# PAGE1.net
KiCad netlist of a schematic drawn in EAGLE
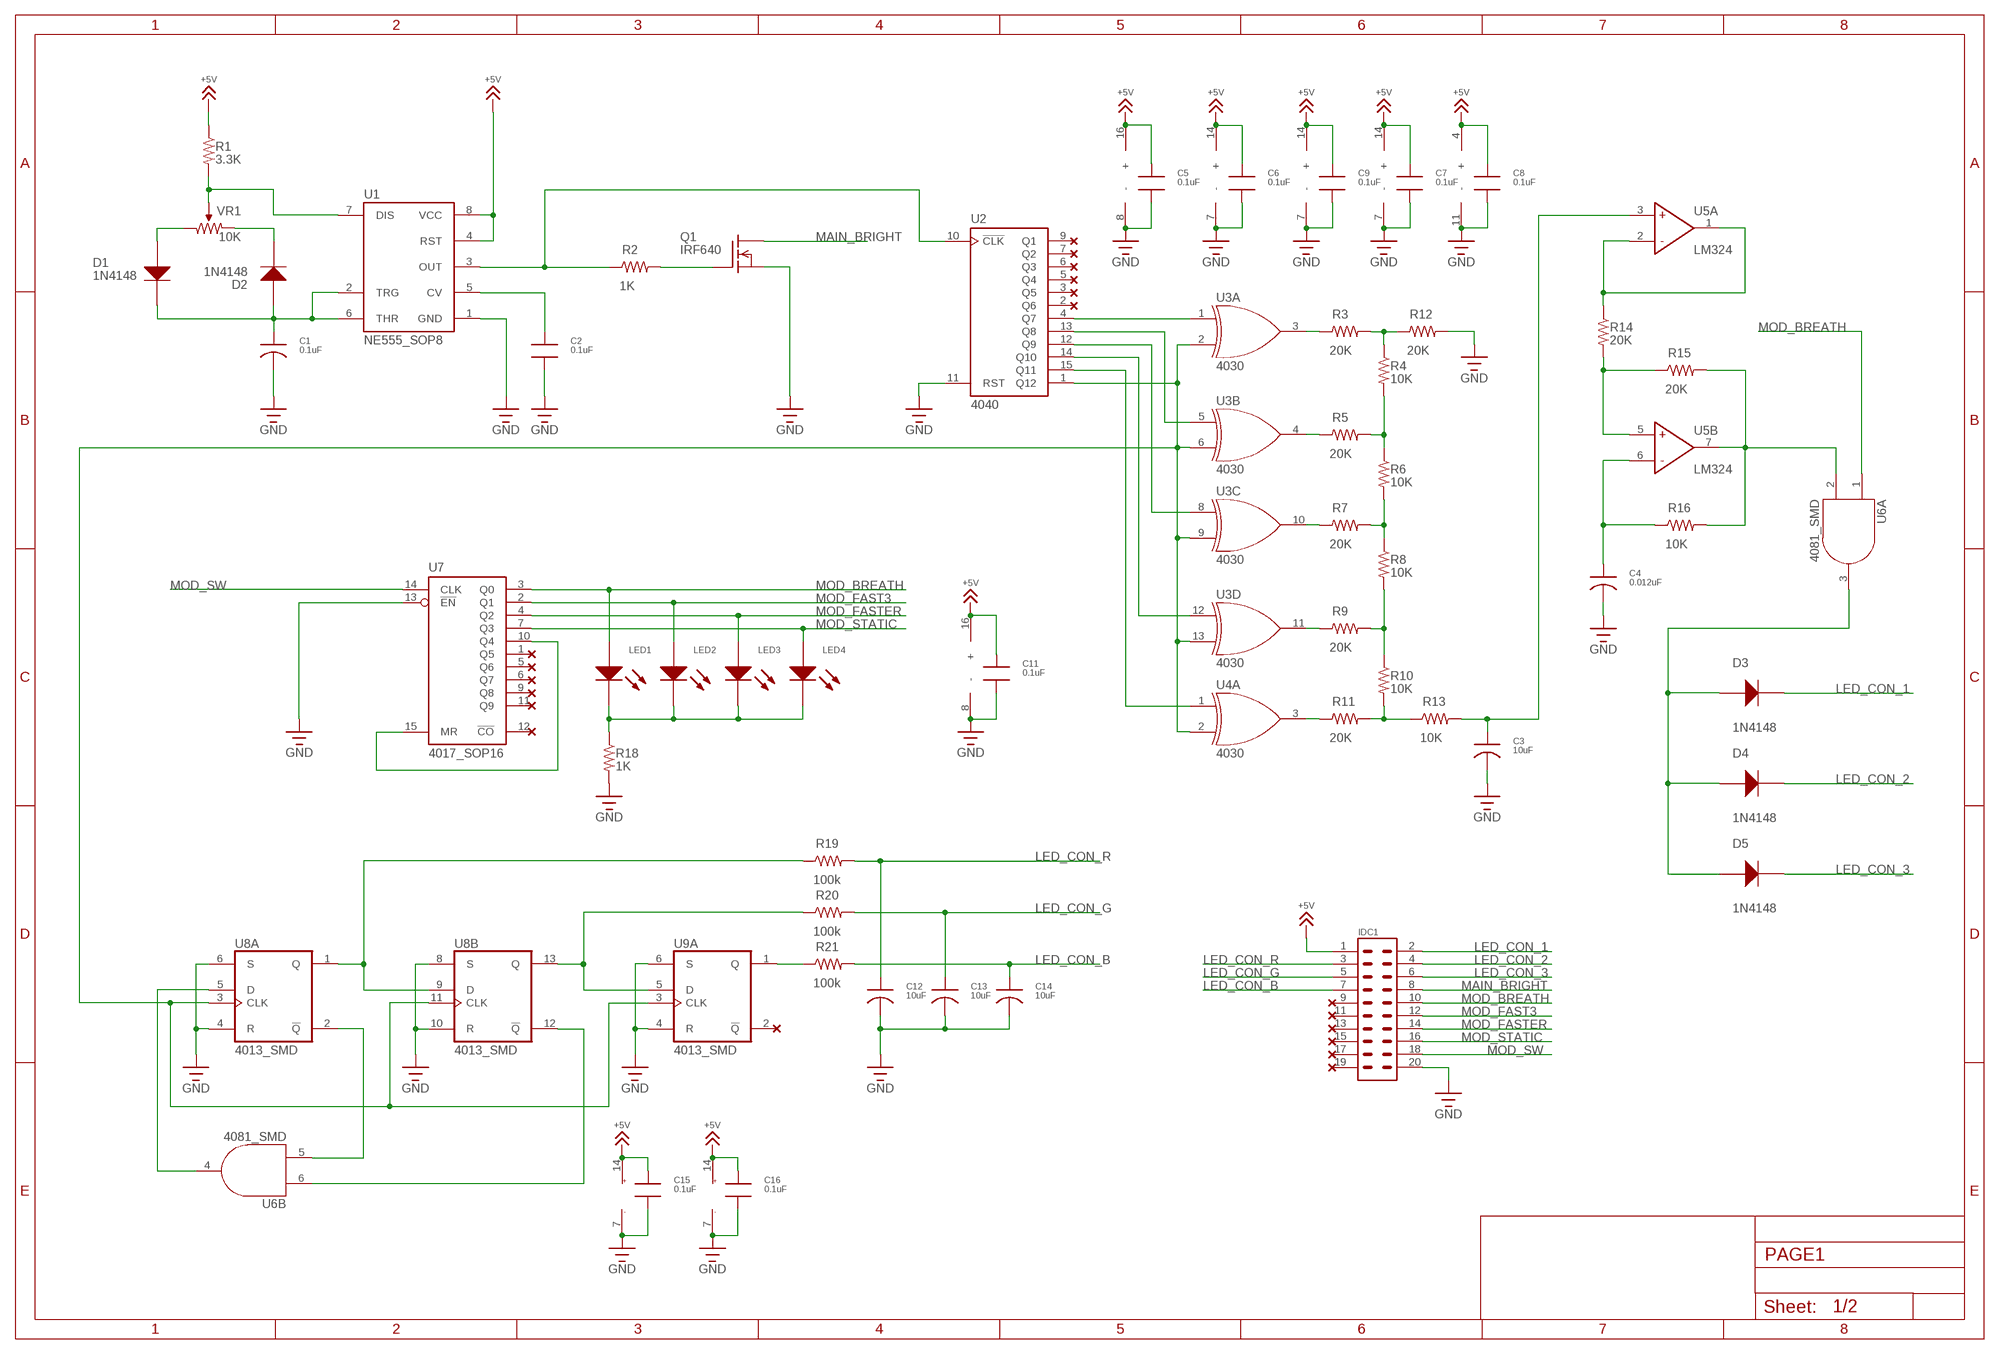
[diagram p0: schematic, sheet 1]
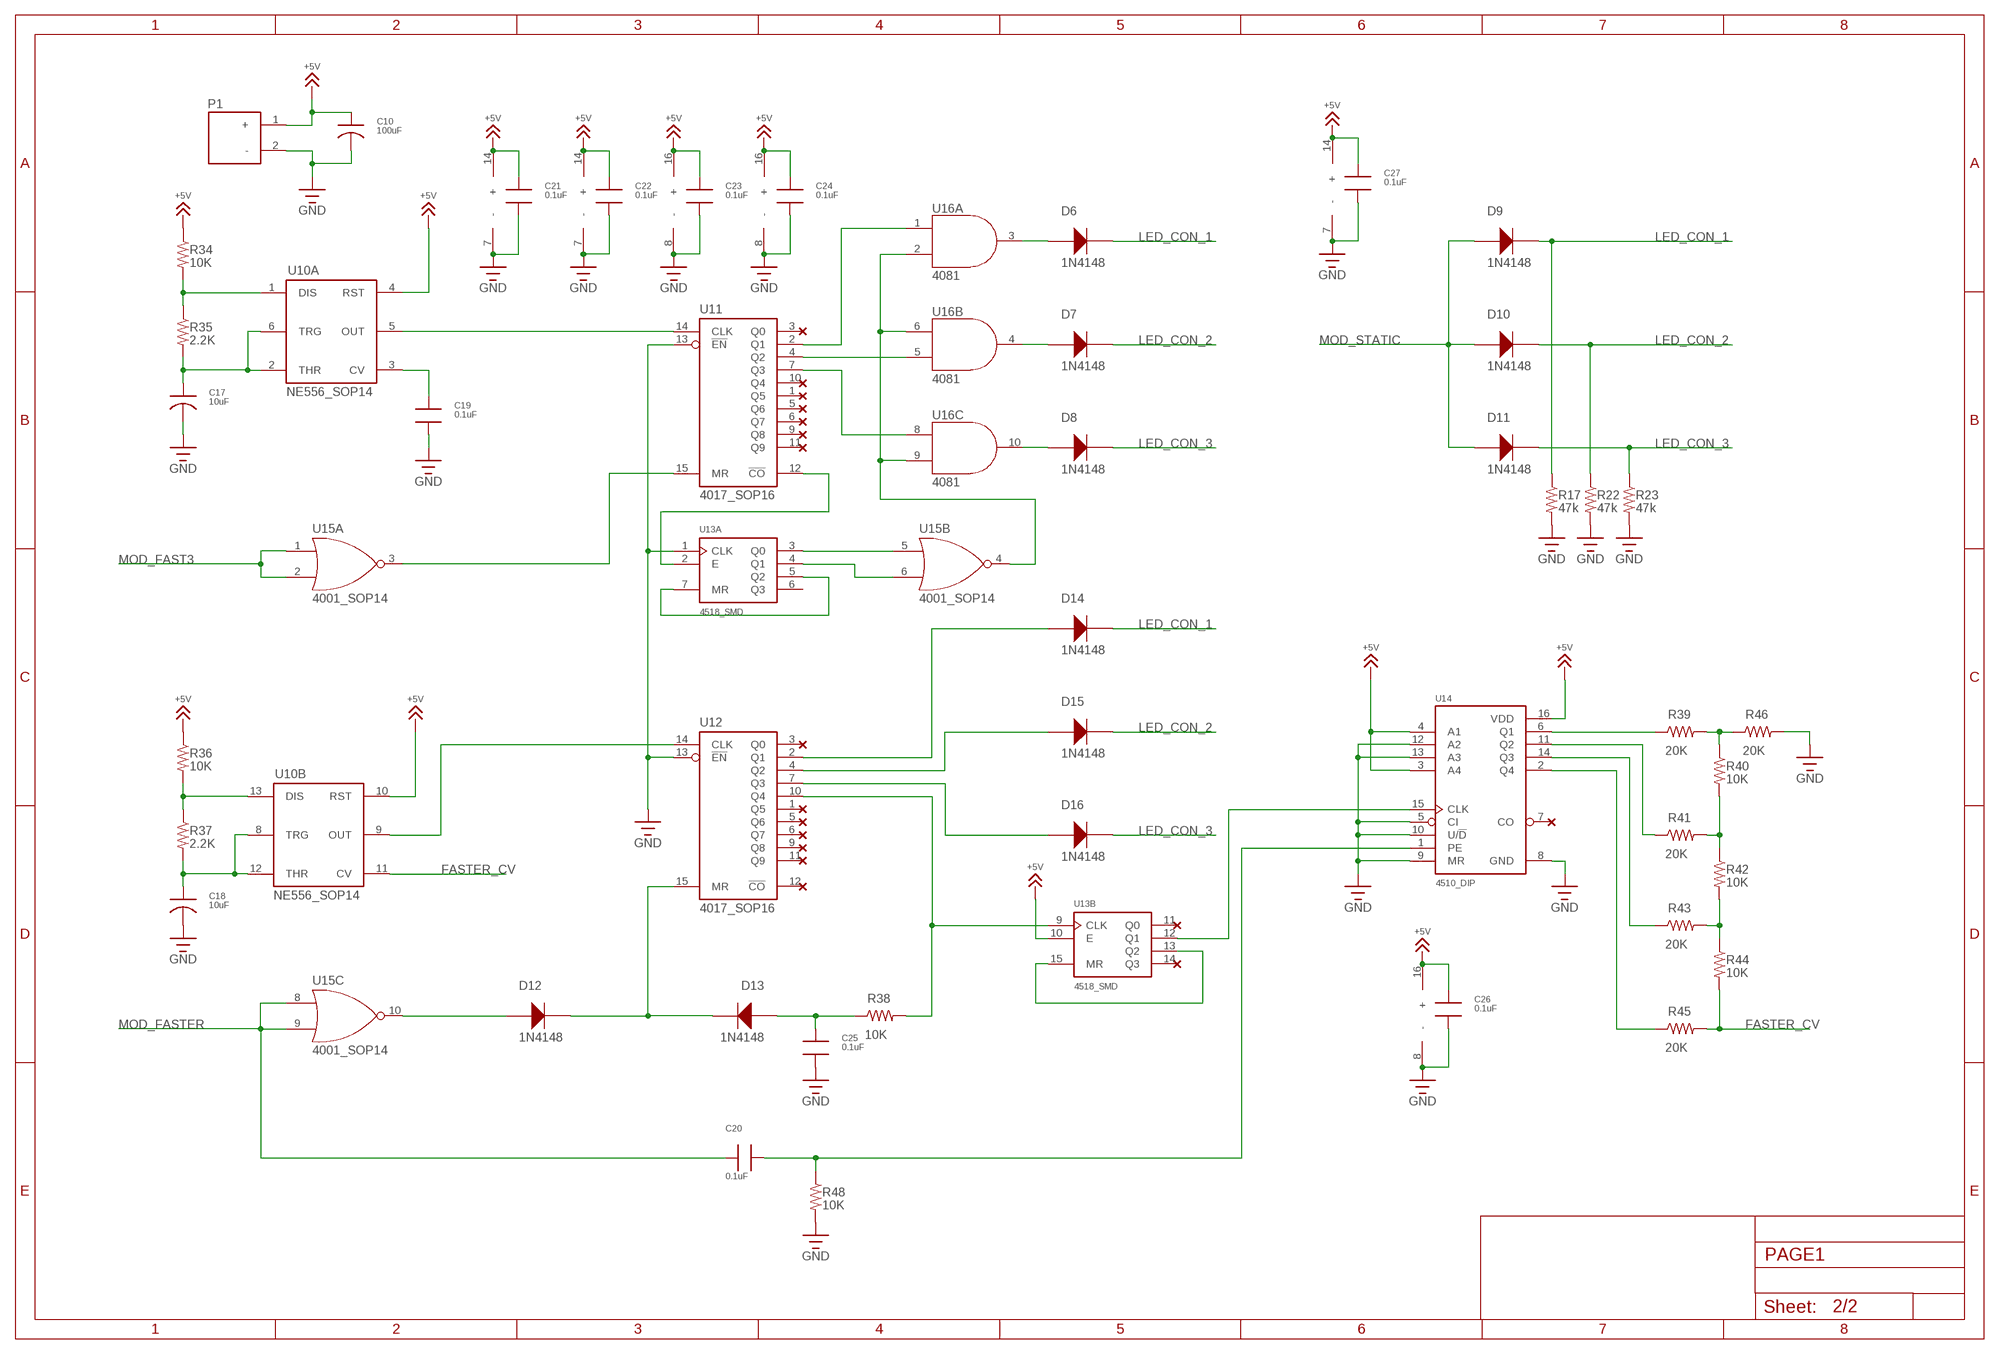
[diagram p1: schematic, sheet 2]

(export (version "E")
  (design (tool "Eeschema 10.0.6"))
  (components
    (comp (ref "C10")
      (value "100uF")
      (footprint "eagle-import:CAP_POL_BIG")
      (libsource (lib "eagle-import") (part "CAP_POL_BIG"))
    )
    (comp (ref "C17")
      (value "10uF")
      (footprint "eagle-import:CAP_POL")
      (libsource (lib "eagle-import") (part "CAP_POL_NOR"))
    )
    (comp (ref "C18")
      (value "10uF")
      (footprint "eagle-import:CAP_POL")
      (libsource (lib "eagle-import") (part "CAP_POL_NOR"))
    )
    (comp (ref "C19")
      (value "0.1uF")
      (footprint "eagle-import:SMD2012")
      (libsource (lib "eagle-import") (part "CAP_NP_SMD2012"))
    )
    (comp (ref "C20")
      (value "0.1uF")
      (footprint "eagle-import:SMD2012")
      (libsource (lib "eagle-import") (part "CAP_NP_SMD2012"))
    )
    (comp (ref "C21")
      (value "0.1uF")
      (footprint "eagle-import:SMD2012")
      (libsource (lib "eagle-import") (part "CAP_NP_SMD2012"))
    )
    (comp (ref "C22")
      (value "0.1uF")
      (footprint "eagle-import:SMD2012")
      (libsource (lib "eagle-import") (part "CAP_NP_SMD2012"))
    )
    (comp (ref "C23")
      (value "0.1uF")
      (footprint "eagle-import:SMD2012")
      (libsource (lib "eagle-import") (part "CAP_NP_SMD2012"))
    )
    (comp (ref "C24")
      (value "0.1uF")
      (footprint "eagle-import:SMD2012")
      (libsource (lib "eagle-import") (part "CAP_NP_SMD2012"))
    )
    (comp (ref "C25")
      (value "0.1uF")
      (footprint "eagle-import:SMD2012")
      (libsource (lib "eagle-import") (part "CAP_NP_SMD2012"))
    )
    (comp (ref "C26")
      (value "0.1uF")
      (footprint "eagle-import:SMD2012")
      (libsource (lib "eagle-import") (part "CAP_NP_SMD2012"))
    )
    (comp (ref "C27")
      (value "0.1uF")
      (footprint "eagle-import:SMD2012")
      (libsource (lib "eagle-import") (part "CAP_NP_SMD2012"))
    )
    (comp (ref "D6")
      (value "1N4148")
      (footprint "eagle-import:SMD_DIODE")
      (libsource (lib "eagle-import") (part "DIODE_SMD"))
    )
    (comp (ref "D7")
      (value "1N4148")
      (footprint "eagle-import:SMD_DIODE")
      (libsource (lib "eagle-import") (part "DIODE_SMD"))
    )
    (comp (ref "D8")
      (value "1N4148")
      (footprint "eagle-import:SMD_DIODE")
      (libsource (lib "eagle-import") (part "DIODE_SMD"))
    )
    (comp (ref "D9")
      (value "1N4148")
      (footprint "eagle-import:SMD_DIODE")
      (libsource (lib "eagle-import") (part "DIODE_SMD"))
    )
    (comp (ref "D10")
      (value "1N4148")
      (footprint "eagle-import:SMD_DIODE")
      (libsource (lib "eagle-import") (part "DIODE_SMD"))
    )
    (comp (ref "D11")
      (value "1N4148")
      (footprint "eagle-import:SMD_DIODE")
      (libsource (lib "eagle-import") (part "DIODE_SMD"))
    )
    (comp (ref "D12")
      (value "1N4148")
      (footprint "eagle-import:SMD_DIODE")
      (libsource (lib "eagle-import") (part "DIODE_SMD"))
    )
    (comp (ref "D13")
      (value "1N4148")
      (footprint "eagle-import:SMD_DIODE")
      (libsource (lib "eagle-import") (part "DIODE_SMD"))
    )
    (comp (ref "D14")
      (value "1N4148")
      (footprint "eagle-import:SMD_DIODE")
      (libsource (lib "eagle-import") (part "DIODE_SMD"))
    )
    (comp (ref "D15")
      (value "1N4148")
      (footprint "eagle-import:SMD_DIODE")
      (libsource (lib "eagle-import") (part "DIODE_SMD"))
    )
    (comp (ref "D16")
      (value "1N4148")
      (footprint "eagle-import:SMD_DIODE")
      (libsource (lib "eagle-import") (part "DIODE_SMD"))
    )
    (comp (ref "P1")
      (value "POWER_2")
      (footprint "eagle-import:POWER_2")
      (libsource (lib "eagle-import") (part "POWER_2"))
    )
    (comp (ref "R17")
      (value "47k")
      (footprint "eagle-import:SMD2012")
      (libsource (lib "eagle-import") (part "RES_2012"))
    )
    (comp (ref "R22")
      (value "47k")
      (footprint "eagle-import:SMD2012")
      (libsource (lib "eagle-import") (part "RES_2012"))
    )
    (comp (ref "R23")
      (value "47k")
      (footprint "eagle-import:SMD2012")
      (libsource (lib "eagle-import") (part "RES_2012"))
    )
    (comp (ref "R34")
      (value "10K")
      (footprint "eagle-import:SMD2012")
      (libsource (lib "eagle-import") (part "RES_2012"))
    )
    (comp (ref "R35")
      (value "2.2K")
      (footprint "eagle-import:SMD2012")
      (libsource (lib "eagle-import") (part "RES_2012"))
    )
    (comp (ref "R36")
      (value "10K")
      (footprint "eagle-import:SMD2012")
      (libsource (lib "eagle-import") (part "RES_2012"))
    )
    (comp (ref "R37")
      (value "2.2K")
      (footprint "eagle-import:SMD2012")
      (libsource (lib "eagle-import") (part "RES_2012"))
    )
    (comp (ref "R38")
      (value "10K")
      (footprint "eagle-import:SMD2012")
      (libsource (lib "eagle-import") (part "RES_2012"))
    )
    (comp (ref "R39")
      (value "20K")
      (footprint "eagle-import:SMD2012")
      (libsource (lib "eagle-import") (part "RES_2012"))
    )
    (comp (ref "R40")
      (value "10K")
      (footprint "eagle-import:SMD2012")
      (libsource (lib "eagle-import") (part "RES_2012"))
    )
    (comp (ref "R41")
      (value "20K")
      (footprint "eagle-import:SMD2012")
      (libsource (lib "eagle-import") (part "RES_2012"))
    )
    (comp (ref "R42")
      (value "10K")
      (footprint "eagle-import:SMD2012")
      (libsource (lib "eagle-import") (part "RES_2012"))
    )
    (comp (ref "R43")
      (value "20K")
      (footprint "eagle-import:SMD2012")
      (libsource (lib "eagle-import") (part "RES_2012"))
    )
    (comp (ref "R44")
      (value "10K")
      (footprint "eagle-import:SMD2012")
      (libsource (lib "eagle-import") (part "RES_2012"))
    )
    (comp (ref "R45")
      (value "20K")
      (footprint "eagle-import:SMD2012")
      (libsource (lib "eagle-import") (part "RES_2012"))
    )
    (comp (ref "R46")
      (value "20K")
      (footprint "eagle-import:SMD2012")
      (libsource (lib "eagle-import") (part "RES_2012"))
    )
    (comp (ref "R48")
      (value "10K")
      (footprint "eagle-import:SMD2012")
      (libsource (lib "eagle-import") (part "RES_2012"))
    )
    (comp (ref "U10")
      (value "NE556_SOP14")
      (footprint "eagle-import:SOP14")
      (libsource (lib "eagle-import") (part "NE556_SOP14"))
    )
    (comp (ref "U11")
      (value "4017_SOP16")
      (footprint "eagle-import:SOP16")
      (libsource (lib "eagle-import") (part "4017_SOP16"))
    )
    (comp (ref "U12")
      (value "4017_SOP16")
      (footprint "eagle-import:SOP16")
      (libsource (lib "eagle-import") (part "4017_SOP16"))
    )
    (comp (ref "U13")
      (value "4518_SMD")
      (footprint "eagle-import:SOP16")
      (libsource (lib "eagle-import") (part "4518_SMD"))
    )
    (comp (ref "U14")
      (value "4510_DIP")
      (footprint "eagle-import:DIP16")
      (libsource (lib "eagle-import") (part "4510_DIP"))
    )
    (comp (ref "U15")
      (value "4001_SOP14")
      (footprint "eagle-import:SOP14")
      (libsource (lib "eagle-import") (part "4001_SOP14"))
    )
    (comp (ref "U16")
      (value "4081")
      (footprint "eagle-import:DIP14")
      (libsource (lib "eagle-import") (part "4081"))
    )
    (comp (ref "C1")
      (value "0.1uF")
      (footprint "eagle-import:CAP_POL")
      (libsource (lib "eagle-import") (part "CAP_POL_NOR"))
    )
    (comp (ref "C2")
      (value "0.1uF")
      (footprint "eagle-import:SMD2012")
      (libsource (lib "eagle-import") (part "CAP_NP_SMD2012"))
    )
    (comp (ref "C3")
      (value "10uF")
      (footprint "eagle-import:CAP_POL")
      (libsource (lib "eagle-import") (part "CAP_POL_NOR"))
    )
    (comp (ref "C4")
      (value "0.012uF")
      (footprint "eagle-import:CAP_POL")
      (libsource (lib "eagle-import") (part "CAP_POL_NOR"))
    )
    (comp (ref "C5")
      (value "0.1uF")
      (footprint "eagle-import:SMD2012")
      (libsource (lib "eagle-import") (part "CAP_NP_SMD2012"))
    )
    (comp (ref "C6")
      (value "0.1uF")
      (footprint "eagle-import:SMD2012")
      (libsource (lib "eagle-import") (part "CAP_NP_SMD2012"))
    )
    (comp (ref "C7")
      (value "0.1uF")
      (footprint "eagle-import:SMD2012")
      (libsource (lib "eagle-import") (part "CAP_NP_SMD2012"))
    )
    (comp (ref "C8")
      (value "0.1uF")
      (footprint "eagle-import:SMD2012")
      (libsource (lib "eagle-import") (part "CAP_NP_SMD2012"))
    )
    (comp (ref "C9")
      (value "0.1uF")
      (footprint "eagle-import:SMD2012")
      (libsource (lib "eagle-import") (part "CAP_NP_SMD2012"))
    )
    (comp (ref "C11")
      (value "0.1uF")
      (footprint "eagle-import:SMD2012")
      (libsource (lib "eagle-import") (part "CAP_NP_SMD2012"))
    )
    (comp (ref "C12")
      (value "10uF")
      (footprint "eagle-import:CAP_POL")
      (libsource (lib "eagle-import") (part "CAP_POL_NOR"))
    )
    (comp (ref "C13")
      (value "10uF")
      (footprint "eagle-import:CAP_POL")
      (libsource (lib "eagle-import") (part "CAP_POL_NOR"))
    )
    (comp (ref "C14")
      (value "10uF")
      (footprint "eagle-import:CAP_POL")
      (libsource (lib "eagle-import") (part "CAP_POL_NOR"))
    )
    (comp (ref "C15")
      (value "0.1uF")
      (footprint "eagle-import:SMD2012")
      (libsource (lib "eagle-import") (part "CAP_NP_SMD2012"))
    )
    (comp (ref "C16")
      (value "0.1uF")
      (footprint "eagle-import:SMD2012")
      (libsource (lib "eagle-import") (part "CAP_NP_SMD2012"))
    )
    (comp (ref "D1")
      (value "1N4148")
      (footprint "eagle-import:SMD_DIODE")
      (libsource (lib "eagle-import") (part "DIODE_SMD"))
    )
    (comp (ref "D2")
      (value "1N4148")
      (footprint "eagle-import:SMD_DIODE")
      (libsource (lib "eagle-import") (part "DIODE_SMD"))
    )
    (comp (ref "D3")
      (value "1N4148")
      (footprint "eagle-import:SMD_DIODE")
      (libsource (lib "eagle-import") (part "DIODE_SMD"))
    )
    (comp (ref "D4")
      (value "1N4148")
      (footprint "eagle-import:SMD_DIODE")
      (libsource (lib "eagle-import") (part "DIODE_SMD"))
    )
    (comp (ref "D5")
      (value "1N4148")
      (footprint "eagle-import:SMD_DIODE")
      (libsource (lib "eagle-import") (part "DIODE_SMD"))
    )
    (comp (ref "IDC1")
      (value "IDC20_BEN")
      (footprint "eagle-import:IDC20_BENDING")
      (libsource (lib "eagle-import") (part "IDC20_BEN"))
    )
    (comp (ref "LED1")
      (value "LED_BEN")
      (footprint "eagle-import:LED_5MM_BEN")
      (libsource (lib "eagle-import") (part "LED_BEN"))
    )
    (comp (ref "LED2")
      (value "LED_BEN")
      (footprint "eagle-import:LED_5MM_BEN")
      (libsource (lib "eagle-import") (part "LED_BEN"))
    )
    (comp (ref "LED3")
      (value "LED_BEN")
      (footprint "eagle-import:LED_5MM_BEN")
      (libsource (lib "eagle-import") (part "LED_BEN"))
    )
    (comp (ref "LED4")
      (value "LED_BEN")
      (footprint "eagle-import:LED_5MM_BEN")
      (libsource (lib "eagle-import") (part "LED_BEN"))
    )
    (comp (ref "Q1")
      (value "IRF640")
      (footprint "eagle-import:TO220")
      (libsource (lib "eagle-import") (part "IRF620"))
    )
    (comp (ref "R1")
      (value "3.3K")
      (footprint "eagle-import:SMD2012")
      (libsource (lib "eagle-import") (part "RES_2012"))
    )
    (comp (ref "R2")
      (value "1K")
      (footprint "eagle-import:SMD2012")
      (libsource (lib "eagle-import") (part "RES_2012"))
    )
    (comp (ref "R3")
      (value "20K")
      (footprint "eagle-import:SMD2012")
      (libsource (lib "eagle-import") (part "RES_2012"))
    )
    (comp (ref "R4")
      (value "10K")
      (footprint "eagle-import:SMD2012")
      (libsource (lib "eagle-import") (part "RES_2012"))
    )
    (comp (ref "R5")
      (value "20K")
      (footprint "eagle-import:SMD2012")
      (libsource (lib "eagle-import") (part "RES_2012"))
    )
    (comp (ref "R6")
      (value "10K")
      (footprint "eagle-import:SMD2012")
      (libsource (lib "eagle-import") (part "RES_2012"))
    )
    (comp (ref "R7")
      (value "20K")
      (footprint "eagle-import:SMD2012")
      (libsource (lib "eagle-import") (part "RES_2012"))
    )
    (comp (ref "R8")
      (value "10K")
      (footprint "eagle-import:SMD2012")
      (libsource (lib "eagle-import") (part "RES_2012"))
    )
    (comp (ref "R9")
      (value "20K")
      (footprint "eagle-import:SMD2012")
      (libsource (lib "eagle-import") (part "RES_2012"))
    )
    (comp (ref "R10")
      (value "10K")
      (footprint "eagle-import:SMD2012")
      (libsource (lib "eagle-import") (part "RES_2012"))
    )
    (comp (ref "R11")
      (value "20K")
      (footprint "eagle-import:SMD2012")
      (libsource (lib "eagle-import") (part "RES_2012"))
    )
    (comp (ref "R12")
      (value "20K")
      (footprint "eagle-import:SMD2012")
      (libsource (lib "eagle-import") (part "RES_2012"))
    )
    (comp (ref "R13")
      (value "10K")
      (footprint "eagle-import:SMD2012")
      (libsource (lib "eagle-import") (part "RES_2012"))
    )
    (comp (ref "R14")
      (value "20K")
      (footprint "eagle-import:SMD2012")
      (libsource (lib "eagle-import") (part "RES_2012"))
    )
    (comp (ref "R15")
      (value "20K")
      (footprint "eagle-import:SMD2012")
      (libsource (lib "eagle-import") (part "RES_2012"))
    )
    (comp (ref "R16")
      (value "10K")
      (footprint "eagle-import:SMD2012")
      (libsource (lib "eagle-import") (part "RES_2012"))
    )
    (comp (ref "R18")
      (value "1K")
      (footprint "eagle-import:SMD2012")
      (libsource (lib "eagle-import") (part "RES_2012"))
    )
    (comp (ref "R19")
      (value "100k")
      (footprint "eagle-import:SMD2012")
      (libsource (lib "eagle-import") (part "RES_2012"))
    )
    (comp (ref "R20")
      (value "100k")
      (footprint "eagle-import:SMD2012")
      (libsource (lib "eagle-import") (part "RES_2012"))
    )
    (comp (ref "R21")
      (value "100k")
      (footprint "eagle-import:SMD2012")
      (libsource (lib "eagle-import") (part "RES_2012"))
    )
    (comp (ref "U1")
      (value "NE555_SOP8")
      (footprint "eagle-import:SOP8")
      (libsource (lib "eagle-import") (part "NE555_SOP8"))
    )
    (comp (ref "U2")
      (value "4040")
      (footprint "eagle-import:DIP16")
      (libsource (lib "eagle-import") (part "4040"))
    )
    (comp (ref "U3")
      (value "4030")
      (footprint "eagle-import:DIP14")
      (libsource (lib "eagle-import") (part "4030"))
    )
    (comp (ref "U4")
      (value "4030")
      (footprint "eagle-import:DIP14")
      (libsource (lib "eagle-import") (part "4030"))
    )
    (comp (ref "U5")
      (value "LM324")
      (footprint "eagle-import:DIP14")
      (libsource (lib "eagle-import") (part "LM324"))
    )
    (comp (ref "U6")
      (value "4081_SMD")
      (footprint "eagle-import:SOP14")
      (libsource (lib "eagle-import") (part "4081_SMD"))
    )
    (comp (ref "U7")
      (value "4017_SOP16")
      (footprint "eagle-import:SOP16")
      (libsource (lib "eagle-import") (part "4017_SOP16"))
    )
    (comp (ref "U8")
      (value "4013_SMD")
      (footprint "eagle-import:SOIC_14")
      (libsource (lib "eagle-import") (part "4013_SMD"))
    )
    (comp (ref "U9")
      (value "4013_SMD")
      (footprint "eagle-import:SOIC_14")
      (libsource (lib "eagle-import") (part "4013_SMD"))
    )
    (comp (ref "VR1")
      (value "10K")
      (footprint "eagle-import:3RP_1610N")
      (libsource (lib "eagle-import") (part "VR_BIG"))
    )
  )
  (nets
    (net (code "1") (name "+5V") (class "Default")
      (node (ref "C10") (pin "1") (pinfunction "1_1") (pintype "passive"))
      (node (ref "C11") (pin "1") (pinfunction "1_1") (pintype "passive"))
      (node (ref "C15") (pin "1") (pinfunction "1_1") (pintype "passive"))
      (node (ref "C16") (pin "1") (pinfunction "1_1") (pintype "passive"))
      (node (ref "C21") (pin "1") (pinfunction "1_1") (pintype "passive"))
      (node (ref "C22") (pin "1") (pinfunction "1_1") (pintype "passive"))
      (node (ref "C23") (pin "1") (pinfunction "1_1") (pintype "passive"))
      (node (ref "C24") (pin "1") (pinfunction "1_1") (pintype "passive"))
      (node (ref "C26") (pin "1") (pinfunction "1_1") (pintype "passive"))
      (node (ref "C27") (pin "1") (pinfunction "1_1") (pintype "passive"))
      (node (ref "C5") (pin "1") (pinfunction "1_1") (pintype "passive"))
      (node (ref "C6") (pin "1") (pinfunction "1_1") (pintype "passive"))
      (node (ref "C7") (pin "1") (pinfunction "1_1") (pintype "passive"))
      (node (ref "C8") (pin "1") (pinfunction "1_1") (pintype "passive"))
      (node (ref "C9") (pin "1") (pinfunction "1_1") (pintype "passive"))
      (node (ref "IDC1") (pin "1") (pinfunction "1_1") (pintype "passive"))
      (node (ref "P1") (pin "1") (pinfunction "+_1") (pintype "passive"))
      (node (ref "R1") (pin "1") (pinfunction "1_1") (pintype "passive"))
      (node (ref "R34") (pin "1") (pinfunction "1_1") (pintype "passive"))
      (node (ref "R36") (pin "1") (pinfunction "1_1") (pintype "passive"))
      (node (ref "U1") (pin "4") (pinfunction "RST_4") (pintype "passive"))
      (node (ref "U1") (pin "8") (pinfunction "VCC_8") (pintype "passive"))
      (node (ref "U10") (pin "10") (pinfunction "RST_10") (pintype "passive"))
      (node (ref "U10") (pin "14") (pinfunction "+_14") (pintype "power_in"))
      (node (ref "U10") (pin "4") (pinfunction "RST_4") (pintype "passive"))
      (node (ref "U11") (pin "16") (pinfunction "+_16") (pintype "power_in"))
      (node (ref "U12") (pin "16") (pinfunction "+_16") (pintype "power_in"))
      (node (ref "U13") (pin "10") (pinfunction "E_10") (pintype "passive"))
      (node (ref "U13") (pin "16") (pinfunction "+_16") (pintype "power_in"))
      (node (ref "U14") (pin "16") (pinfunction "VDD_16") (pintype "power_in"))
      (node (ref "U14") (pin "3") (pinfunction "A4_3") (pintype "input"))
      (node (ref "U14") (pin "4") (pinfunction "A1_4") (pintype "input"))
      (node (ref "U15") (pin "14") (pinfunction "+_14") (pintype "power_in"))
      (node (ref "U16") (pin "14") (pinfunction "+_14") (pintype "power_in"))
      (node (ref "U2") (pin "16") (pinfunction "+_16") (pintype "power_in"))
      (node (ref "U3") (pin "14") (pinfunction "+_14") (pintype "power_in"))
      (node (ref "U4") (pin "14") (pinfunction "+_14") (pintype "power_in"))
      (node (ref "U5") (pin "4") (pinfunction "+_4") (pintype "power_in"))
      (node (ref "U6") (pin "14") (pinfunction "+_14") (pintype "power_in"))
      (node (ref "U7") (pin "16") (pinfunction "+_16") (pintype "power_in"))
      (node (ref "U8") (pin "14") (pinfunction "VCC_14") (pintype "power_in"))
      (node (ref "U9") (pin "14") (pinfunction "VCC_14") (pintype "power_in"))
    )
    (net (code "2") (name "FASTER_CV") (class "Default")
      (node (ref "R44") (pin "2") (pinfunction "2_2") (pintype "passive"))
      (node (ref "R45") (pin "2") (pinfunction "2_2") (pintype "passive"))
      (node (ref "U10") (pin "11") (pinfunction "CV_11") (pintype "passive"))
    )
    (net (code "3") (name "GND") (class "Default")
      (node (ref "C1") (pin "2") (pinfunction "2_2") (pintype "passive"))
      (node (ref "C10") (pin "2") (pinfunction "2_2") (pintype "passive"))
      (node (ref "C11") (pin "2") (pinfunction "2_2") (pintype "passive"))
      (node (ref "C12") (pin "2") (pinfunction "2_2") (pintype "passive"))
      (node (ref "C13") (pin "2") (pinfunction "2_2") (pintype "passive"))
      (node (ref "C14") (pin "2") (pinfunction "2_2") (pintype "passive"))
      (node (ref "C15") (pin "2") (pinfunction "2_2") (pintype "passive"))
      (node (ref "C16") (pin "2") (pinfunction "2_2") (pintype "passive"))
      (node (ref "C17") (pin "2") (pinfunction "2_2") (pintype "passive"))
      (node (ref "C18") (pin "2") (pinfunction "2_2") (pintype "passive"))
      (node (ref "C19") (pin "2") (pinfunction "2_2") (pintype "passive"))
      (node (ref "C2") (pin "2") (pinfunction "2_2") (pintype "passive"))
      (node (ref "C21") (pin "2") (pinfunction "2_2") (pintype "passive"))
      (node (ref "C22") (pin "2") (pinfunction "2_2") (pintype "passive"))
      (node (ref "C23") (pin "2") (pinfunction "2_2") (pintype "passive"))
      (node (ref "C24") (pin "2") (pinfunction "2_2") (pintype "passive"))
      (node (ref "C25") (pin "2") (pinfunction "2_2") (pintype "passive"))
      (node (ref "C26") (pin "2") (pinfunction "2_2") (pintype "passive"))
      (node (ref "C27") (pin "2") (pinfunction "2_2") (pintype "passive"))
      (node (ref "C3") (pin "2") (pinfunction "2_2") (pintype "passive"))
      (node (ref "C4") (pin "2") (pinfunction "2_2") (pintype "passive"))
      (node (ref "C5") (pin "2") (pinfunction "2_2") (pintype "passive"))
      (node (ref "C6") (pin "2") (pinfunction "2_2") (pintype "passive"))
      (node (ref "C7") (pin "2") (pinfunction "2_2") (pintype "passive"))
      (node (ref "C8") (pin "2") (pinfunction "2_2") (pintype "passive"))
      (node (ref "C9") (pin "2") (pinfunction "2_2") (pintype "passive"))
      (node (ref "IDC1") (pin "20") (pinfunction "20_20") (pintype "passive"))
      (node (ref "P1") (pin "2") (pinfunction "-_2") (pintype "passive"))
      (node (ref "Q1") (pin "3") (pinfunction "S_3") (pintype "passive"))
      (node (ref "R12") (pin "2") (pinfunction "2_2") (pintype "passive"))
      (node (ref "R17") (pin "2") (pinfunction "2_2") (pintype "passive"))
      (node (ref "R18") (pin "2") (pinfunction "2_2") (pintype "passive"))
      (node (ref "R22") (pin "2") (pinfunction "2_2") (pintype "passive"))
      (node (ref "R23") (pin "2") (pinfunction "2_2") (pintype "passive"))
      (node (ref "R46") (pin "2") (pinfunction "2_2") (pintype "passive"))
      (node (ref "R48") (pin "2") (pinfunction "2_2") (pintype "passive"))
      (node (ref "U1") (pin "1") (pinfunction "GND_1") (pintype "passive"))
      (node (ref "U10") (pin "7") (pinfunction "-_7") (pintype "power_in"))
      (node (ref "U11") (pin "13") (pinfunction "~{EN}_13") (pintype "passive"))
      (node (ref "U11") (pin "8") (pinfunction "-_8") (pintype "power_in"))
      (node (ref "U12") (pin "13") (pinfunction "~{EN}_13") (pintype "passive"))
      (node (ref "U12") (pin "8") (pinfunction "-_8") (pintype "power_in"))
      (node (ref "U13") (pin "1") (pinfunction "CLK_1") (pintype "input"))
      (node (ref "U13") (pin "8") (pinfunction "-_8") (pintype "power_in"))
      (node (ref "U14") (pin "10") (pinfunction "U/~{D}_10") (pintype "passive"))
      (node (ref "U14") (pin "12") (pinfunction "A2_12") (pintype "input"))
      (node (ref "U14") (pin "13") (pinfunction "A3_13") (pintype "input"))
      (node (ref "U14") (pin "5") (pinfunction "CI_5") (pintype "input"))
      (node (ref "U14") (pin "8") (pinfunction "GND_8") (pintype "power_in"))
      (node (ref "U14") (pin "9") (pinfunction "MR_9") (pintype "passive"))
      (node (ref "U15") (pin "7") (pinfunction "-_7") (pintype "power_in"))
      (node (ref "U16") (pin "7") (pinfunction "-_7") (pintype "power_in"))
      (node (ref "U2") (pin "11") (pinfunction "RST_11") (pintype "input"))
      (node (ref "U2") (pin "8") (pinfunction "-_8") (pintype "power_in"))
      (node (ref "U3") (pin "7") (pinfunction "-_7") (pintype "power_in"))
      (node (ref "U4") (pin "7") (pinfunction "-_7") (pintype "power_in"))
      (node (ref "U5") (pin "11") (pinfunction "-_11") (pintype "power_in"))
      (node (ref "U6") (pin "7") (pinfunction "-_7") (pintype "power_in"))
      (node (ref "U7") (pin "13") (pinfunction "~{EN}_13") (pintype "passive"))
      (node (ref "U7") (pin "8") (pinfunction "-_8") (pintype "power_in"))
      (node (ref "U8") (pin "10") (pinfunction "R_10") (pintype "input"))
      (node (ref "U8") (pin "4") (pinfunction "R_4") (pintype "input"))
      (node (ref "U8") (pin "6") (pinfunction "S_6") (pintype "input"))
      (node (ref "U8") (pin "7") (pinfunction "GND_7") (pintype "power_in"))
      (node (ref "U8") (pin "8") (pinfunction "S_8") (pintype "input"))
      (node (ref "U9") (pin "4") (pinfunction "R_4") (pintype "input"))
      (node (ref "U9") (pin "6") (pinfunction "S_6") (pintype "input"))
      (node (ref "U9") (pin "7") (pinfunction "GND_7") (pintype "power_in"))
    )
    (net (code "4") (name "LED_CON_1") (class "Default")
      (node (ref "D14") (pin "2") (pinfunction "2_2") (pintype "passive"))
      (node (ref "D3") (pin "2") (pinfunction "2_2") (pintype "passive"))
      (node (ref "D6") (pin "2") (pinfunction "2_2") (pintype "passive"))
      (node (ref "D9") (pin "2") (pinfunction "2_2") (pintype "passive"))
      (node (ref "IDC1") (pin "2") (pinfunction "2_2") (pintype "passive"))
      (node (ref "R17") (pin "1") (pinfunction "1_1") (pintype "passive"))
    )
    (net (code "5") (name "LED_CON_2") (class "Default")
      (node (ref "D10") (pin "2") (pinfunction "2_2") (pintype "passive"))
      (node (ref "D15") (pin "2") (pinfunction "2_2") (pintype "passive"))
      (node (ref "D4") (pin "2") (pinfunction "2_2") (pintype "passive"))
      (node (ref "D7") (pin "2") (pinfunction "2_2") (pintype "passive"))
      (node (ref "IDC1") (pin "4") (pinfunction "4_4") (pintype "passive"))
      (node (ref "R22") (pin "1") (pinfunction "1_1") (pintype "passive"))
    )
    (net (code "6") (name "LED_CON_3") (class "Default")
      (node (ref "D11") (pin "2") (pinfunction "2_2") (pintype "passive"))
      (node (ref "D16") (pin "2") (pinfunction "2_2") (pintype "passive"))
      (node (ref "D5") (pin "2") (pinfunction "2_2") (pintype "passive"))
      (node (ref "D8") (pin "2") (pinfunction "2_2") (pintype "passive"))
      (node (ref "IDC1") (pin "6") (pinfunction "6_6") (pintype "passive"))
      (node (ref "R23") (pin "1") (pinfunction "1_1") (pintype "passive"))
    )
    (net (code "7") (name "LED_CON_B") (class "Default")
      (node (ref "C14") (pin "1") (pinfunction "1_1") (pintype "passive"))
      (node (ref "IDC1") (pin "7") (pinfunction "7_7") (pintype "passive"))
      (node (ref "R21") (pin "2") (pinfunction "2_2") (pintype "passive"))
    )
    (net (code "8") (name "LED_CON_G") (class "Default")
      (node (ref "C13") (pin "1") (pinfunction "1_1") (pintype "passive"))
      (node (ref "IDC1") (pin "5") (pinfunction "5_5") (pintype "passive"))
      (node (ref "R20") (pin "2") (pinfunction "2_2") (pintype "passive"))
    )
    (net (code "9") (name "LED_CON_R") (class "Default")
      (node (ref "C12") (pin "1") (pinfunction "1_1") (pintype "passive"))
      (node (ref "IDC1") (pin "3") (pinfunction "3_3") (pintype "passive"))
      (node (ref "R19") (pin "2") (pinfunction "2_2") (pintype "passive"))
    )
    (net (code "10") (name "MAIN_BRIGHT") (class "Default")
      (node (ref "IDC1") (pin "8") (pinfunction "8_8") (pintype "passive"))
      (node (ref "Q1") (pin "2") (pinfunction "D_2") (pintype "passive"))
    )
    (net (code "11") (name "MOD_BREATH") (class "Default")
      (node (ref "IDC1") (pin "10") (pinfunction "10_10") (pintype "passive"))
      (node (ref "LED1") (pin "1") (pinfunction "P$1_1") (pintype "passive"))
      (node (ref "U6") (pin "1") (pinfunction "P$1_1") (pintype "passive"))
      (node (ref "U7") (pin "3") (pinfunction "Q0_3") (pintype "output"))
    )
    (net (code "12") (name "MOD_FAST3") (class "Default")
      (node (ref "IDC1") (pin "12") (pinfunction "12_12") (pintype "passive"))
      (node (ref "LED2") (pin "1") (pinfunction "P$1_1") (pintype "passive"))
      (node (ref "U15") (pin "1") (pinfunction "IN1_1") (pintype "passive"))
      (node (ref "U15") (pin "2") (pinfunction "IN2_2") (pintype "passive"))
      (node (ref "U7") (pin "2") (pinfunction "Q1_2") (pintype "output"))
    )
    (net (code "13") (name "MOD_FASTER") (class "Default")
      (node (ref "C20") (pin "1") (pinfunction "1_1") (pintype "passive"))
      (node (ref "IDC1") (pin "14") (pinfunction "14_14") (pintype "passive"))
      (node (ref "LED3") (pin "1") (pinfunction "P$1_1") (pintype "passive"))
      (node (ref "U15") (pin "8") (pinfunction "IN1_8") (pintype "passive"))
      (node (ref "U15") (pin "9") (pinfunction "IN2_9") (pintype "passive"))
      (node (ref "U7") (pin "4") (pinfunction "Q2_4") (pintype "output"))
    )
    (net (code "14") (name "MOD_STATIC") (class "Default")
      (node (ref "D10") (pin "1") (pinfunction "1_1") (pintype "passive"))
      (node (ref "D11") (pin "1") (pinfunction "1_1") (pintype "passive"))
      (node (ref "D9") (pin "1") (pinfunction "1_1") (pintype "passive"))
      (node (ref "IDC1") (pin "16") (pinfunction "16_16") (pintype "passive"))
      (node (ref "LED4") (pin "1") (pinfunction "P$1_1") (pintype "passive"))
      (node (ref "U7") (pin "7") (pinfunction "Q3_7") (pintype "output"))
    )
    (net (code "15") (name "MOD_SW") (class "Default")
      (node (ref "IDC1") (pin "18") (pinfunction "18_18") (pintype "passive"))
      (node (ref "U7") (pin "14") (pinfunction "CLK_14") (pintype "passive"))
    )
    (net (code "16") (name "Net-(C25-Pad1)") (class "Default")
      (node (ref "C25") (pin "1") (pinfunction "1_1") (pintype "passive"))
      (node (ref "D13") (pin "1") (pinfunction "1_1") (pintype "passive"))
      (node (ref "R38") (pin "1") (pinfunction "1_1") (pintype "passive"))
    )
    (net (code "17") (name "Net-(D1-Pad1)") (class "Default")
      (node (ref "D1") (pin "1") (pinfunction "1_1") (pintype "passive"))
      (node (ref "VR1") (pin "1") (pinfunction "1_1") (pintype "passive"))
    )
    (net (code "18") (name "Net-(D2-Pad2)") (class "Default")
      (node (ref "D2") (pin "2") (pinfunction "2_2") (pintype "passive"))
      (node (ref "VR1") (pin "3") (pinfunction "3_3") (pintype "passive"))
    )
    (net (code "19") (name "Net-(LED1-P$2)") (class "Default")
      (node (ref "LED1") (pin "2") (pinfunction "P$2_2") (pintype "passive"))
      (node (ref "LED2") (pin "2") (pinfunction "P$2_2") (pintype "passive"))
      (node (ref "LED3") (pin "2") (pinfunction "P$2_2") (pintype "passive"))
      (node (ref "LED4") (pin "2") (pinfunction "P$2_2") (pintype "passive"))
      (node (ref "R18") (pin "1") (pinfunction "1_1") (pintype "passive"))
    )
    (net (code "20") (name "Net-(Q1-G)") (class "Default")
      (node (ref "Q1") (pin "1") (pinfunction "G_1") (pintype "passive"))
      (node (ref "R2") (pin "2") (pinfunction "2_2") (pintype "passive"))
    )
    (net (code "21") (name "Net-(R4-Pad2)") (class "Default")
      (node (ref "R4") (pin "2") (pinfunction "2_2") (pintype "passive"))
      (node (ref "R5") (pin "2") (pinfunction "2_2") (pintype "passive"))
      (node (ref "R6") (pin "1") (pinfunction "1_1") (pintype "passive"))
    )
    (net (code "22") (name "Net-(R6-Pad2)") (class "Default")
      (node (ref "R6") (pin "2") (pinfunction "2_2") (pintype "passive"))
      (node (ref "R7") (pin "2") (pinfunction "2_2") (pintype "passive"))
      (node (ref "R8") (pin "1") (pinfunction "1_1") (pintype "passive"))
    )
    (net (code "23") (name "Net-(R10-Pad1)") (class "Default")
      (node (ref "R10") (pin "1") (pinfunction "1_1") (pintype "passive"))
      (node (ref "R8") (pin "2") (pinfunction "2_2") (pintype "passive"))
      (node (ref "R9") (pin "2") (pinfunction "2_2") (pintype "passive"))
    )
    (net (code "24") (name "Net-(R10-Pad2)") (class "Default")
      (node (ref "R10") (pin "2") (pinfunction "2_2") (pintype "passive"))
      (node (ref "R11") (pin "2") (pinfunction "2_2") (pintype "passive"))
      (node (ref "R13") (pin "1") (pinfunction "1_1") (pintype "passive"))
    )
    (net (code "25") (name "Net-(R12-Pad1)") (class "Default")
      (node (ref "R12") (pin "1") (pinfunction "1_1") (pintype "passive"))
      (node (ref "R3") (pin "2") (pinfunction "2_2") (pintype "passive"))
      (node (ref "R4") (pin "1") (pinfunction "1_1") (pintype "passive"))
    )
    (net (code "26") (name "Net-(R39-Pad2)") (class "Default")
      (node (ref "R39") (pin "2") (pinfunction "2_2") (pintype "passive"))
      (node (ref "R40") (pin "1") (pinfunction "1_1") (pintype "passive"))
      (node (ref "R46") (pin "1") (pinfunction "1_1") (pintype "passive"))
    )
    (net (code "27") (name "Net-(R40-Pad2)") (class "Default")
      (node (ref "R40") (pin "2") (pinfunction "2_2") (pintype "passive"))
      (node (ref "R41") (pin "2") (pinfunction "2_2") (pintype "passive"))
      (node (ref "R42") (pin "1") (pinfunction "1_1") (pintype "passive"))
    )
    (net (code "28") (name "Net-(R42-Pad2)") (class "Default")
      (node (ref "R42") (pin "2") (pinfunction "2_2") (pintype "passive"))
      (node (ref "R43") (pin "2") (pinfunction "2_2") (pintype "passive"))
      (node (ref "R44") (pin "1") (pinfunction "1_1") (pintype "passive"))
    )
    (net (code "29") (name "Net-(U1-CV)") (class "Default")
      (node (ref "C2") (pin "1") (pinfunction "1_1") (pintype "passive"))
      (node (ref "U1") (pin "5") (pinfunction "CV_5") (pintype "passive"))
    )
    (net (code "30") (name "Net-(U1-DIS)") (class "Default")
      (node (ref "R1") (pin "2") (pinfunction "2_2") (pintype "passive"))
      (node (ref "U1") (pin "7") (pinfunction "DIS_7") (pintype "passive"))
      (node (ref "VR1") (pin "2") (pinfunction "2_2") (pintype "passive"))
    )
    (net (code "31") (name "Net-(U1-OUT)") (class "Default")
      (node (ref "R2") (pin "1") (pinfunction "1_1") (pintype "passive"))
      (node (ref "U1") (pin "3") (pinfunction "OUT_3") (pintype "passive"))
      (node (ref "U2") (pin "10") (pinfunction "~{CLK}_10") (pintype "input"))
    )
    (net (code "32") (name "Net-(U1-THR)") (class "Default")
      (node (ref "C1") (pin "1") (pinfunction "1_1") (pintype "passive"))
      (node (ref "D1") (pin "2") (pinfunction "2_2") (pintype "passive"))
      (node (ref "D2") (pin "1") (pinfunction "1_1") (pintype "passive"))
      (node (ref "U1") (pin "2") (pinfunction "TRG_2") (pintype "passive"))
      (node (ref "U1") (pin "6") (pinfunction "THR_6") (pintype "passive"))
    )
    (net (code "33") (name "Net-(U2A-Q7)") (class "Default")
      (node (ref "U2") (pin "4") (pinfunction "Q7_4") (pintype "output"))
      (node (ref "U3") (pin "1") (pinfunction "IN1_1") (pintype "passive"))
    )
    (net (code "34") (name "Net-(U2A-Q8)") (class "Default")
      (node (ref "U2") (pin "13") (pinfunction "Q8_13") (pintype "output"))
      (node (ref "U3") (pin "5") (pinfunction "IN1_5") (pintype "passive"))
    )
    (net (code "35") (name "Net-(U2A-Q9)") (class "Default")
      (node (ref "U2") (pin "12") (pinfunction "Q9_12") (pintype "output"))
      (node (ref "U3") (pin "8") (pinfunction "IN1_8") (pintype "passive"))
    )
    (net (code "36") (name "Net-(U2A-Q10)") (class "Default")
      (node (ref "U2") (pin "14") (pinfunction "Q10_14") (pintype "output"))
      (node (ref "U3") (pin "12") (pinfunction "IN1_12") (pintype "passive"))
    )
    (net (code "37") (name "Net-(U2A-Q11)") (class "Default")
      (node (ref "U2") (pin "15") (pinfunction "Q11_15") (pintype "output"))
      (node (ref "U4") (pin "1") (pinfunction "IN1_1") (pintype "passive"))
    )
    (net (code "38") (name "Net-(U2A-Q12)") (class "Default")
      (node (ref "U2") (pin "1") (pinfunction "Q12_1") (pintype "output"))
      (node (ref "U3") (pin "13") (pinfunction "IN2_13") (pintype "passive"))
      (node (ref "U3") (pin "2") (pinfunction "IN2_2") (pintype "passive"))
      (node (ref "U3") (pin "6") (pinfunction "IN2_6") (pintype "passive"))
      (node (ref "U3") (pin "9") (pinfunction "IN2_9") (pintype "passive"))
      (node (ref "U4") (pin "2") (pinfunction "IN2_2") (pintype "passive"))
      (node (ref "U8") (pin "11") (pinfunction "CLK_11") (pintype "input"))
      (node (ref "U8") (pin "3") (pinfunction "CLK_3") (pintype "input"))
      (node (ref "U9") (pin "3") (pinfunction "CLK_3") (pintype "input"))
    )
    (net (code "39") (name "Net-(U3A-OUT)") (class "Default")
      (node (ref "R3") (pin "1") (pinfunction "1_1") (pintype "passive"))
      (node (ref "U3") (pin "3") (pinfunction "OUT_3") (pintype "passive"))
    )
    (net (code "40") (name "Net-(U3B-OUT)") (class "Default")
      (node (ref "R5") (pin "1") (pinfunction "1_1") (pintype "passive"))
      (node (ref "U3") (pin "4") (pinfunction "OUT_4") (pintype "passive"))
    )
    (net (code "41") (name "Net-(U3C-OUT)") (class "Default")
      (node (ref "R7") (pin "1") (pinfunction "1_1") (pintype "passive"))
      (node (ref "U3") (pin "10") (pinfunction "OUT_10") (pintype "passive"))
    )
    (net (code "42") (name "Net-(U3D-OUT)") (class "Default")
      (node (ref "R9") (pin "1") (pinfunction "1_1") (pintype "passive"))
      (node (ref "U3") (pin "11") (pinfunction "OUT_11") (pintype "passive"))
    )
    (net (code "43") (name "Net-(U4A-OUT)") (class "Default")
      (node (ref "R11") (pin "1") (pinfunction "1_1") (pintype "passive"))
      (node (ref "U4") (pin "3") (pinfunction "OUT_3") (pintype "passive"))
    )
    (net (code "44") (name "Net-(U5A-+)") (class "Default")
      (node (ref "C3") (pin "1") (pinfunction "1_1") (pintype "passive"))
      (node (ref "R13") (pin "2") (pinfunction "2_2") (pintype "passive"))
      (node (ref "U5") (pin "3") (pinfunction "+_3") (pintype "input"))
    )
    (net (code "45") (name "Net-(U5A--)") (class "Default")
      (node (ref "R14") (pin "1") (pinfunction "1_1") (pintype "passive"))
      (node (ref "U5") (pin "1") (pinfunction "OUT_1") (pintype "output"))
      (node (ref "U5") (pin "2") (pinfunction "-_2") (pintype "input"))
    )
    (net (code "46") (name "Net-(U5B-+)") (class "Default")
      (node (ref "R14") (pin "2") (pinfunction "2_2") (pintype "passive"))
      (node (ref "R15") (pin "1") (pinfunction "1_1") (pintype "passive"))
      (node (ref "U5") (pin "5") (pinfunction "+_5") (pintype "input"))
    )
    (net (code "47") (name "Net-(U5B--)") (class "Default")
      (node (ref "C4") (pin "1") (pinfunction "1_1") (pintype "passive"))
      (node (ref "R16") (pin "1") (pinfunction "1_1") (pintype "passive"))
      (node (ref "U5") (pin "6") (pinfunction "-_6") (pintype "input"))
    )
    (net (code "48") (name "Net-(U5B-OUT)") (class "Default")
      (node (ref "R15") (pin "2") (pinfunction "2_2") (pintype "passive"))
      (node (ref "R16") (pin "2") (pinfunction "2_2") (pintype "passive"))
      (node (ref "U5") (pin "7") (pinfunction "OUT_7") (pintype "output"))
      (node (ref "U6") (pin "2") (pinfunction "P$2_2") (pintype "passive"))
    )
    (net (code "49") (name "Net-(U6A-P$3)") (class "Default")
      (node (ref "D3") (pin "1") (pinfunction "1_1") (pintype "passive"))
      (node (ref "D4") (pin "1") (pinfunction "1_1") (pintype "passive"))
      (node (ref "D5") (pin "1") (pinfunction "1_1") (pintype "passive"))
      (node (ref "U6") (pin "3") (pinfunction "P$3_3") (pintype "passive"))
    )
    (net (code "50") (name "Net-(U6B-P$1)") (class "Default")
      (node (ref "U6") (pin "6") (pinfunction "P$1_6") (pintype "passive"))
      (node (ref "U8") (pin "12") (pinfunction "~{Q}_12") (pintype "output"))
    )
    (net (code "51") (name "Net-(U6B-P$2)") (class "Default")
      (node (ref "U6") (pin "5") (pinfunction "P$2_5") (pintype "passive"))
      (node (ref "U8") (pin "2") (pinfunction "~{Q}_2") (pintype "output"))
    )
    (net (code "52") (name "Net-(U6B-P$3)") (class "Default")
      (node (ref "U6") (pin "4") (pinfunction "P$3_4") (pintype "passive"))
      (node (ref "U8") (pin "5") (pinfunction "D_5") (pintype "input"))
    )
    (net (code "53") (name "Net-(U7A-MR)") (class "Default")
      (node (ref "U7") (pin "10") (pinfunction "Q4_10") (pintype "output"))
      (node (ref "U7") (pin "15") (pinfunction "MR_15") (pintype "passive"))
    )
    (net (code "54") (name "Net-(U8A-Q)") (class "Default")
      (node (ref "R19") (pin "1") (pinfunction "1_1") (pintype "passive"))
      (node (ref "U8") (pin "1") (pinfunction "Q_1") (pintype "output"))
      (node (ref "U8") (pin "9") (pinfunction "D_9") (pintype "input"))
    )
    (net (code "55") (name "Net-(U8B-Q)") (class "Default")
      (node (ref "R20") (pin "1") (pinfunction "1_1") (pintype "passive"))
      (node (ref "U8") (pin "13") (pinfunction "Q_13") (pintype "output"))
      (node (ref "U9") (pin "5") (pinfunction "D_5") (pintype "input"))
    )
    (net (code "56") (name "Net-(U9A-Q)") (class "Default")
      (node (ref "R21") (pin "1") (pinfunction "1_1") (pintype "passive"))
      (node (ref "U9") (pin "1") (pinfunction "Q_1") (pintype "output"))
    )
    (net (code "57") (name "Net-(U10A-CV)") (class "Default")
      (node (ref "C19") (pin "1") (pinfunction "1_1") (pintype "passive"))
      (node (ref "U10") (pin "3") (pinfunction "CV_3") (pintype "passive"))
    )
    (net (code "58") (name "Net-(U10A-DIS)") (class "Default")
      (node (ref "R34") (pin "2") (pinfunction "2_2") (pintype "passive"))
      (node (ref "R35") (pin "1") (pinfunction "1_1") (pintype "passive"))
      (node (ref "U10") (pin "1") (pinfunction "DIS_1") (pintype "passive"))
    )
    (net (code "59") (name "Net-(U10A-OUT)") (class "Default")
      (node (ref "U10") (pin "5") (pinfunction "OUT_5") (pintype "passive"))
      (node (ref "U11") (pin "14") (pinfunction "CLK_14") (pintype "passive"))
    )
    (net (code "60") (name "Net-(U10A-THR)") (class "Default")
      (node (ref "C17") (pin "1") (pinfunction "1_1") (pintype "passive"))
      (node (ref "R35") (pin "2") (pinfunction "2_2") (pintype "passive"))
      (node (ref "U10") (pin "2") (pinfunction "THR_2") (pintype "passive"))
      (node (ref "U10") (pin "6") (pinfunction "TRG_6") (pintype "passive"))
    )
    (net (code "61") (name "Net-(U10B-DIS)") (class "Default")
      (node (ref "R36") (pin "2") (pinfunction "2_2") (pintype "passive"))
      (node (ref "R37") (pin "1") (pinfunction "1_1") (pintype "passive"))
      (node (ref "U10") (pin "13") (pinfunction "DIS_13") (pintype "passive"))
    )
    (net (code "62") (name "Net-(U10B-OUT)") (class "Default")
      (node (ref "U10") (pin "9") (pinfunction "OUT_9") (pintype "passive"))
      (node (ref "U12") (pin "14") (pinfunction "CLK_14") (pintype "passive"))
    )
    (net (code "63") (name "Net-(U10B-THR)") (class "Default")
      (node (ref "C18") (pin "1") (pinfunction "1_1") (pintype "passive"))
      (node (ref "R37") (pin "2") (pinfunction "2_2") (pintype "passive"))
      (node (ref "U10") (pin "12") (pinfunction "THR_12") (pintype "passive"))
      (node (ref "U10") (pin "8") (pinfunction "TRG_8") (pintype "passive"))
    )
    (net (code "64") (name "Net-(U11A-MR)") (class "Default")
      (node (ref "U11") (pin "15") (pinfunction "MR_15") (pintype "passive"))
      (node (ref "U15") (pin "3") (pinfunction "OUT_3") (pintype "passive"))
    )
    (net (code "65") (name "Net-(U11A-Q1)") (class "Default")
      (node (ref "U11") (pin "2") (pinfunction "Q1_2") (pintype "output"))
      (node (ref "U16") (pin "1") (pinfunction "P$1_1") (pintype "passive"))
    )
    (net (code "66") (name "Net-(U11A-Q2)") (class "Default")
      (node (ref "U11") (pin "4") (pinfunction "Q2_4") (pintype "output"))
      (node (ref "U16") (pin "5") (pinfunction "P$2_5") (pintype "passive"))
    )
    (net (code "67") (name "Net-(U11A-Q3)") (class "Default")
      (node (ref "U11") (pin "7") (pinfunction "Q3_7") (pintype "output"))
      (node (ref "U16") (pin "8") (pinfunction "P$1_8") (pintype "passive"))
    )
    (net (code "68") (name "Net-(U11A-~{CO})") (class "Default")
      (node (ref "U11") (pin "12") (pinfunction "~{CO}_12") (pintype "output"))
      (node (ref "U13") (pin "2") (pinfunction "E_2") (pintype "passive"))
    )
    (net (code "69") (name "Net-(U12A-MR)") (class "Default")
      (node (ref "D12") (pin "2") (pinfunction "2_2") (pintype "passive"))
      (node (ref "D13") (pin "2") (pinfunction "2_2") (pintype "passive"))
      (node (ref "U12") (pin "15") (pinfunction "MR_15") (pintype "passive"))
    )
    (net (code "70") (name "Net-(U12A-Q1)") (class "Default")
      (node (ref "D14") (pin "1") (pinfunction "1_1") (pintype "passive"))
      (node (ref "U12") (pin "2") (pinfunction "Q1_2") (pintype "output"))
    )
    (net (code "71") (name "Net-(U12A-Q2)") (class "Default")
      (node (ref "D15") (pin "1") (pinfunction "1_1") (pintype "passive"))
      (node (ref "U12") (pin "4") (pinfunction "Q2_4") (pintype "output"))
    )
    (net (code "72") (name "Net-(U12A-Q3)") (class "Default")
      (node (ref "D16") (pin "1") (pinfunction "1_1") (pintype "passive"))
      (node (ref "U12") (pin "7") (pinfunction "Q3_7") (pintype "output"))
    )
    (net (code "73") (name "Net-(U12A-Q4)") (class "Default")
      (node (ref "R38") (pin "2") (pinfunction "2_2") (pintype "passive"))
      (node (ref "U12") (pin "10") (pinfunction "Q4_10") (pintype "output"))
      (node (ref "U13") (pin "9") (pinfunction "CLK_9") (pintype "input"))
    )
    (net (code "74") (name "Net-(U13A-MR)") (class "Default")
      (node (ref "U13") (pin "5") (pinfunction "Q2_5") (pintype "output"))
      (node (ref "U13") (pin "7") (pinfunction "MR_7") (pintype "passive"))
    )
    (net (code "75") (name "Net-(U13A-Q0)") (class "Default")
      (node (ref "U13") (pin "3") (pinfunction "Q0_3") (pintype "output"))
      (node (ref "U15") (pin "5") (pinfunction "IN1_5") (pintype "passive"))
    )
    (net (code "76") (name "Net-(U13A-Q1)") (class "Default")
      (node (ref "U13") (pin "4") (pinfunction "Q1_4") (pintype "output"))
      (node (ref "U15") (pin "6") (pinfunction "IN2_6") (pintype "passive"))
    )
    (net (code "77") (name "Net-(U13B-MR)") (class "Default")
      (node (ref "U13") (pin "13") (pinfunction "Q2_13") (pintype "output"))
      (node (ref "U13") (pin "15") (pinfunction "MR_15") (pintype "passive"))
    )
    (net (code "78") (name "Net-(U13B-Q1)") (class "Default")
      (node (ref "U13") (pin "12") (pinfunction "Q1_12") (pintype "output"))
      (node (ref "U14") (pin "15") (pinfunction "CLK_15") (pintype "input"))
    )
    (net (code "79") (name "Net-(U14-PE)") (class "Default")
      (node (ref "C20") (pin "2") (pinfunction "2_2") (pintype "passive"))
      (node (ref "R48") (pin "1") (pinfunction "1_1") (pintype "passive"))
      (node (ref "U14") (pin "1") (pinfunction "PE_1") (pintype "passive"))
    )
    (net (code "80") (name "Net-(U14-Q1)") (class "Default")
      (node (ref "R39") (pin "1") (pinfunction "1_1") (pintype "passive"))
      (node (ref "U14") (pin "6") (pinfunction "Q1_6") (pintype "output"))
    )
    (net (code "81") (name "Net-(U14-Q2)") (class "Default")
      (node (ref "R41") (pin "1") (pinfunction "1_1") (pintype "passive"))
      (node (ref "U14") (pin "11") (pinfunction "Q2_11") (pintype "output"))
    )
    (net (code "82") (name "Net-(U14-Q3)") (class "Default")
      (node (ref "R43") (pin "1") (pinfunction "1_1") (pintype "passive"))
      (node (ref "U14") (pin "14") (pinfunction "Q3_14") (pintype "output"))
    )
    (net (code "83") (name "Net-(U14-Q4)") (class "Default")
      (node (ref "R45") (pin "1") (pinfunction "1_1") (pintype "passive"))
      (node (ref "U14") (pin "2") (pinfunction "Q4_2") (pintype "output"))
    )
    (net (code "84") (name "Net-(U15B-OUT)") (class "Default")
      (node (ref "U15") (pin "4") (pinfunction "OUT_4") (pintype "passive"))
      (node (ref "U16") (pin "2") (pinfunction "P$2_2") (pintype "passive"))
      (node (ref "U16") (pin "6") (pinfunction "P$1_6") (pintype "passive"))
      (node (ref "U16") (pin "9") (pinfunction "P$2_9") (pintype "passive"))
    )
    (net (code "85") (name "Net-(U15C-OUT)") (class "Default")
      (node (ref "D12") (pin "1") (pinfunction "1_1") (pintype "passive"))
      (node (ref "U15") (pin "10") (pinfunction "OUT_10") (pintype "passive"))
    )
    (net (code "86") (name "Net-(U16A-P$3)") (class "Default")
      (node (ref "D6") (pin "1") (pinfunction "1_1") (pintype "passive"))
      (node (ref "U16") (pin "3") (pinfunction "P$3_3") (pintype "passive"))
    )
    (net (code "87") (name "Net-(U16B-P$3)") (class "Default")
      (node (ref "D7") (pin "1") (pinfunction "1_1") (pintype "passive"))
      (node (ref "U16") (pin "4") (pinfunction "P$3_4") (pintype "passive"))
    )
    (net (code "88") (name "Net-(U16C-P$3)") (class "Default")
      (node (ref "D8") (pin "1") (pinfunction "1_1") (pintype "passive"))
      (node (ref "U16") (pin "10") (pinfunction "P$3_10") (pintype "passive"))
    )
    (net (code "89") (name "unconnected-(IDC1-Pad9)") (class "Default")
      (node (ref "IDC1") (pin "9") (pinfunction "9_9") (pintype "passive"))
    )
    (net (code "90") (name "unconnected-(IDC1-Pad11)") (class "Default")
      (node (ref "IDC1") (pin "11") (pinfunction "11_11") (pintype "passive"))
    )
    (net (code "91") (name "unconnected-(IDC1-Pad13)") (class "Default")
      (node (ref "IDC1") (pin "13") (pinfunction "13_13") (pintype "passive"))
    )
    (net (code "92") (name "unconnected-(IDC1-Pad15)") (class "Default")
      (node (ref "IDC1") (pin "15") (pinfunction "15_15") (pintype "passive"))
    )
    (net (code "93") (name "unconnected-(IDC1-Pad17)") (class "Default")
      (node (ref "IDC1") (pin "17") (pinfunction "17_17") (pintype "passive"))
    )
    (net (code "94") (name "unconnected-(IDC1-Pad19)") (class "Default")
      (node (ref "IDC1") (pin "19") (pinfunction "19_19") (pintype "passive"))
    )
    (net (code "95") (name "unconnected-(U2A-Q1-Pad9)") (class "Default")
      (node (ref "U2") (pin "9") (pinfunction "Q1_9") (pintype "output"))
    )
    (net (code "96") (name "unconnected-(U2A-Q2-Pad7)") (class "Default")
      (node (ref "U2") (pin "7") (pinfunction "Q2_7") (pintype "output"))
    )
    (net (code "97") (name "unconnected-(U2A-Q3-Pad6)") (class "Default")
      (node (ref "U2") (pin "6") (pinfunction "Q3_6") (pintype "output"))
    )
    (net (code "98") (name "unconnected-(U2A-Q4-Pad5)") (class "Default")
      (node (ref "U2") (pin "5") (pinfunction "Q4_5") (pintype "output"))
    )
    (net (code "99") (name "unconnected-(U2A-Q5-Pad3)") (class "Default")
      (node (ref "U2") (pin "3") (pinfunction "Q5_3") (pintype "output"))
    )
    (net (code "100") (name "unconnected-(U2A-Q6-Pad2)") (class "Default")
      (node (ref "U2") (pin "2") (pinfunction "Q6_2") (pintype "output"))
    )
    (net (code "101") (name "unconnected-(U7A-Q5-Pad1)") (class "Default")
      (node (ref "U7") (pin "1") (pinfunction "Q5_1") (pintype "output"))
    )
    (net (code "102") (name "unconnected-(U7A-Q6-Pad5)") (class "Default")
      (node (ref "U7") (pin "5") (pinfunction "Q6_5") (pintype "output"))
    )
    (net (code "103") (name "unconnected-(U7A-Q7-Pad6)") (class "Default")
      (node (ref "U7") (pin "6") (pinfunction "Q7_6") (pintype "output"))
    )
    (net (code "104") (name "unconnected-(U7A-Q8-Pad9)") (class "Default")
      (node (ref "U7") (pin "9") (pinfunction "Q8_9") (pintype "output"))
    )
    (net (code "105") (name "unconnected-(U7A-Q9-Pad11)") (class "Default")
      (node (ref "U7") (pin "11") (pinfunction "Q9_11") (pintype "output"))
    )
    (net (code "106") (name "unconnected-(U7A-~{CO}-Pad12)") (class "Default")
      (node (ref "U7") (pin "12") (pinfunction "~{CO}_12") (pintype "output"))
    )
    (net (code "107") (name "unconnected-(U9A-~{Q}-Pad2)") (class "Default")
      (node (ref "U9") (pin "2") (pinfunction "~{Q}_2") (pintype "output"))
    )
    (net (code "108") (name "unconnected-(U11A-Q0-Pad3)") (class "Default")
      (node (ref "U11") (pin "3") (pinfunction "Q0_3") (pintype "output"))
    )
    (net (code "109") (name "unconnected-(U11A-Q4-Pad10)") (class "Default")
      (node (ref "U11") (pin "10") (pinfunction "Q4_10") (pintype "output"))
    )
    (net (code "110") (name "unconnected-(U11A-Q5-Pad1)") (class "Default")
      (node (ref "U11") (pin "1") (pinfunction "Q5_1") (pintype "output"))
    )
    (net (code "111") (name "unconnected-(U11A-Q6-Pad5)") (class "Default")
      (node (ref "U11") (pin "5") (pinfunction "Q6_5") (pintype "output"))
    )
    (net (code "112") (name "unconnected-(U11A-Q7-Pad6)") (class "Default")
      (node (ref "U11") (pin "6") (pinfunction "Q7_6") (pintype "output"))
    )
    (net (code "113") (name "unconnected-(U11A-Q8-Pad9)") (class "Default")
      (node (ref "U11") (pin "9") (pinfunction "Q8_9") (pintype "output"))
    )
    (net (code "114") (name "unconnected-(U11A-Q9-Pad11)") (class "Default")
      (node (ref "U11") (pin "11") (pinfunction "Q9_11") (pintype "output"))
    )
    (net (code "115") (name "unconnected-(U12A-Q0-Pad3)") (class "Default")
      (node (ref "U12") (pin "3") (pinfunction "Q0_3") (pintype "output"))
    )
    (net (code "116") (name "unconnected-(U12A-Q5-Pad1)") (class "Default")
      (node (ref "U12") (pin "1") (pinfunction "Q5_1") (pintype "output"))
    )
    (net (code "117") (name "unconnected-(U12A-Q6-Pad5)") (class "Default")
      (node (ref "U12") (pin "5") (pinfunction "Q6_5") (pintype "output"))
    )
    (net (code "118") (name "unconnected-(U12A-Q7-Pad6)") (class "Default")
      (node (ref "U12") (pin "6") (pinfunction "Q7_6") (pintype "output"))
    )
    (net (code "119") (name "unconnected-(U12A-Q8-Pad9)") (class "Default")
      (node (ref "U12") (pin "9") (pinfunction "Q8_9") (pintype "output"))
    )
    (net (code "120") (name "unconnected-(U12A-Q9-Pad11)") (class "Default")
      (node (ref "U12") (pin "11") (pinfunction "Q9_11") (pintype "output"))
    )
    (net (code "121") (name "unconnected-(U12A-~{CO}-Pad12)") (class "Default")
      (node (ref "U12") (pin "12") (pinfunction "~{CO}_12") (pintype "output"))
    )
    (net (code "122") (name "unconnected-(U13A-Q3-Pad6)") (class "Default")
      (node (ref "U13") (pin "6") (pinfunction "Q3_6") (pintype "output"))
    )
    (net (code "123") (name "unconnected-(U13B-Q0-Pad11)") (class "Default")
      (node (ref "U13") (pin "11") (pinfunction "Q0_11") (pintype "output"))
    )
    (net (code "124") (name "unconnected-(U13B-Q3-Pad14)") (class "Default")
      (node (ref "U13") (pin "14") (pinfunction "Q3_14") (pintype "output"))
    )
    (net (code "125") (name "unconnected-(U14-CO-Pad7)") (class "Default")
      (node (ref "U14") (pin "7") (pinfunction "CO_7") (pintype "output"))
    )
  )
)
